# voltage-and-current-display-hw.net
KiCad netlist of a schematic drawn in Altium Designer
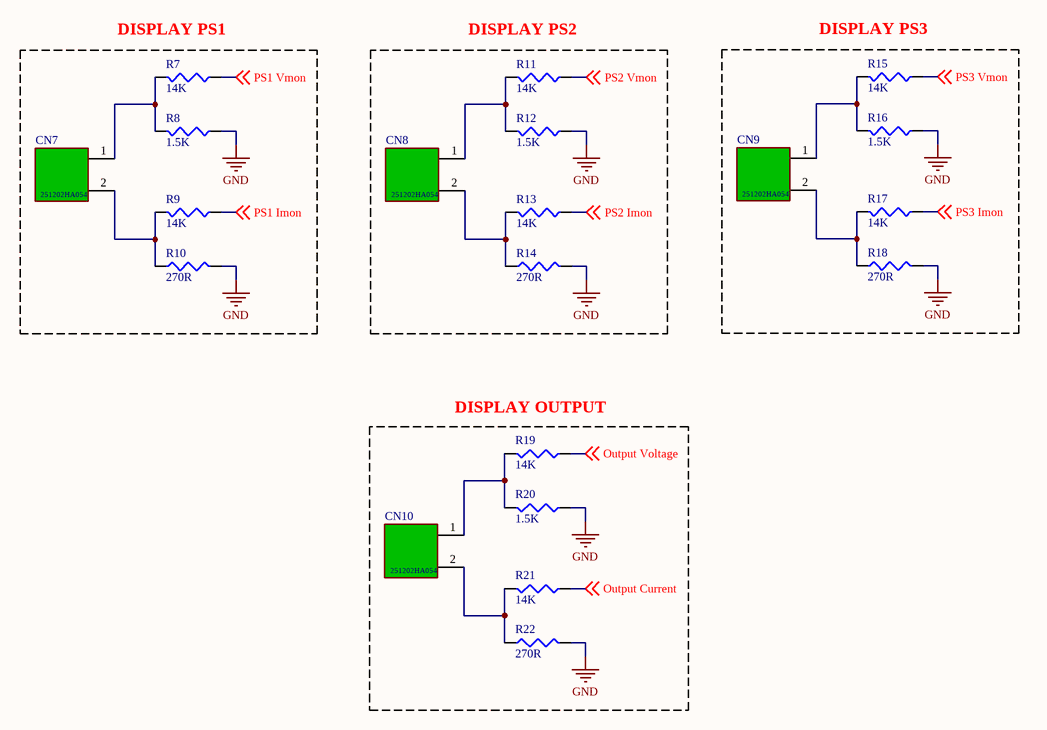
[diagram p0: voltage-and-current-display-hw.SchDoc]

(export (version "E")
  (design (tool "Eeschema 10.0.6"))
  (components
    (comp (ref "CN7")
      (value "Header 2 Pin 251202HA054")
      (footprint "CONECTOR KK EXCON 251202HA054")
      (libsource (lib "acopians-monitoring-hw-library-schematic") (part "CONECTOR KK EXCON 251202HA054"))
    )
    (comp (ref "CN8")
      (value "Header 2 Pin 251202HA054")
      (footprint "CONECTOR KK EXCON 251202HA054")
      (libsource (lib "acopians-monitoring-hw-library-schematic") (part "CONECTOR KK EXCON 251202HA054"))
    )
    (comp (ref "CN9")
      (value "Header 2 Pin 251202HA054")
      (footprint "CONECTOR KK EXCON 251202HA054")
      (libsource (lib "acopians-monitoring-hw-library-schematic") (part "CONECTOR KK EXCON 251202HA054"))
    )
    (comp (ref "CN10")
      (value "Header 2 Pin 251202HA054")
      (footprint "CONECTOR KK EXCON 251202HA054")
      (libsource (lib "acopians-monitoring-hw-library-schematic") (part "CONECTOR KK EXCON 251202HA054"))
    )
    (comp (ref "R7")
      (value "14K")
      (footprint "R0603")
      (description "Resistor SMD 14K OHM 0.1% 1/10W 0603")
      (fields (field (name "TOLERANCE") "0.1%"))
      (libsource (lib "acopians-monitoring-hw-library-schematic") (part "RESISTOR 14K"))
    )
    (comp (ref "R8")
      (value "1.5K")
      (footprint "R0603")
      (description "Resistor SMD 1.5K OHM 0.1% 1/10W 0603")
      (fields (field (name "TOLERANCE") "0.1%"))
      (libsource (lib "acopians-monitoring-hw-library-schematic") (part "RESISTOR 1.5K"))
    )
    (comp (ref "R9")
      (value "14K")
      (footprint "R0603")
      (description "Resistor SMD 14K OHM 0.1% 1/10W 0603")
      (fields (field (name "TOLERANCE") "0.1%"))
      (libsource (lib "acopians-monitoring-hw-library-schematic") (part "RESISTOR 14K"))
    )
    (comp (ref "R10")
      (value "270R")
      (footprint "R0603")
      (description "Resistor SMD 270 OHM 1% 1/10W 0603")
      (fields (field (name "TOLERANCE") "1%"))
      (libsource (lib "acopians-monitoring-hw-library-schematic") (part "RESISTOR 270R"))
    )
    (comp (ref "R11")
      (value "14K")
      (footprint "R0603")
      (description "Resistor SMD 14K OHM 0.1% 1/10W 0603")
      (fields (field (name "TOLERANCE") "0.1%"))
      (libsource (lib "acopians-monitoring-hw-library-schematic") (part "RESISTOR 14K"))
    )
    (comp (ref "R12")
      (value "1.5K")
      (footprint "R0603")
      (description "Resistor SMD 1.5K OHM 0.1% 1/10W 0603")
      (fields (field (name "TOLERANCE") "0.1%"))
      (libsource (lib "acopians-monitoring-hw-library-schematic") (part "RESISTOR 1.5K"))
    )
    (comp (ref "R13")
      (value "14K")
      (footprint "R0603")
      (description "Resistor SMD 14K OHM 0.1% 1/10W 0603")
      (fields (field (name "TOLERANCE") "0.1%"))
      (libsource (lib "acopians-monitoring-hw-library-schematic") (part "RESISTOR 14K"))
    )
    (comp (ref "R14")
      (value "270R")
      (footprint "R0603")
      (description "Resistor SMD 270 OHM 1% 1/10W 0603")
      (fields (field (name "TOLERANCE") "1%"))
      (libsource (lib "acopians-monitoring-hw-library-schematic") (part "RESISTOR 270R"))
    )
    (comp (ref "R15")
      (value "14K")
      (footprint "R0603")
      (description "Resistor SMD 14K OHM 0.1% 1/10W 0603")
      (fields (field (name "TOLERANCE") "0.1%"))
      (libsource (lib "acopians-monitoring-hw-library-schematic") (part "RESISTOR 14K"))
    )
    (comp (ref "R16")
      (value "1.5K")
      (footprint "R0603")
      (description "Resistor SMD 1.5K OHM 0.1% 1/10W 0603")
      (fields (field (name "TOLERANCE") "0.1%"))
      (libsource (lib "acopians-monitoring-hw-library-schematic") (part "RESISTOR 1.5K"))
    )
    (comp (ref "R17")
      (value "14K")
      (footprint "R0603")
      (description "Resistor SMD 14K OHM 0.1% 1/10W 0603")
      (fields (field (name "TOLERANCE") "0.1%"))
      (libsource (lib "acopians-monitoring-hw-library-schematic") (part "RESISTOR 14K"))
    )
    (comp (ref "R18")
      (value "270R")
      (footprint "R0603")
      (description "Resistor SMD 270 OHM 1% 1/10W 0603")
      (fields (field (name "TOLERANCE") "1%"))
      (libsource (lib "acopians-monitoring-hw-library-schematic") (part "RESISTOR 270R"))
    )
    (comp (ref "R19")
      (value "14K")
      (footprint "R0603")
      (description "Resistor SMD 14K OHM 0.1% 1/10W 0603")
      (fields (field (name "TOLERANCE") "0.1%"))
      (libsource (lib "acopians-monitoring-hw-library-schematic") (part "RESISTOR 14K"))
    )
    (comp (ref "R20")
      (value "1.5K")
      (footprint "R0603")
      (description "Resistor SMD 1.5K OHM 0.1% 1/10W 0603")
      (fields (field (name "TOLERANCE") "0.1%"))
      (libsource (lib "acopians-monitoring-hw-library-schematic") (part "RESISTOR 1.5K"))
    )
    (comp (ref "R21")
      (value "14K")
      (footprint "R0603")
      (description "Resistor SMD 14K OHM 0.1% 1/10W 0603")
      (fields (field (name "TOLERANCE") "0.1%"))
      (libsource (lib "acopians-monitoring-hw-library-schematic") (part "RESISTOR 14K"))
    )
    (comp (ref "R22")
      (value "270R")
      (footprint "R0603")
      (description "Resistor SMD 270 OHM 1% 1/10W 0603")
      (fields (field (name "TOLERANCE") "1%"))
      (libsource (lib "acopians-monitoring-hw-library-schematic") (part "RESISTOR 270R"))
    )
  )
  (nets
    (net (code "1") (name "GND") (class "Default")
      (node (ref "R10") (pin "2") (pinfunction "2_2") (pintype "passive"))
      (node (ref "R12") (pin "1") (pinfunction "1_1") (pintype "passive"))
      (node (ref "R14") (pin "2") (pinfunction "2_2") (pintype "passive"))
      (node (ref "R16") (pin "1") (pinfunction "1_1") (pintype "passive"))
      (node (ref "R18") (pin "2") (pinfunction "2_2") (pintype "passive"))
      (node (ref "R20") (pin "1") (pinfunction "1_1") (pintype "passive"))
      (node (ref "R22") (pin "2") (pinfunction "2_2") (pintype "passive"))
      (node (ref "R8") (pin "1") (pinfunction "1_1") (pintype "passive"))
    )
    (net (code "2") (name "Net-(CN7-Pad1)") (class "Default")
      (node (ref "CN7") (pin "1") (pinfunction "1_1") (pintype "passive"))
      (node (ref "R7") (pin "2") (pinfunction "2_2") (pintype "passive"))
      (node (ref "R8") (pin "2") (pinfunction "2_2") (pintype "passive"))
    )
    (net (code "3") (name "Net-(CN7-Pad2)") (class "Default")
      (node (ref "CN7") (pin "2") (pinfunction "2_2") (pintype "passive"))
      (node (ref "R10") (pin "1") (pinfunction "1_1") (pintype "passive"))
      (node (ref "R9") (pin "2") (pinfunction "2_2") (pintype "passive"))
    )
    (net (code "4") (name "Net-(CN8-Pad1)") (class "Default")
      (node (ref "CN8") (pin "1") (pinfunction "1_1") (pintype "passive"))
      (node (ref "R11") (pin "2") (pinfunction "2_2") (pintype "passive"))
      (node (ref "R12") (pin "2") (pinfunction "2_2") (pintype "passive"))
    )
    (net (code "5") (name "Net-(CN8-Pad2)") (class "Default")
      (node (ref "CN8") (pin "2") (pinfunction "2_2") (pintype "passive"))
      (node (ref "R13") (pin "2") (pinfunction "2_2") (pintype "passive"))
      (node (ref "R14") (pin "1") (pinfunction "1_1") (pintype "passive"))
    )
    (net (code "6") (name "Net-(CN9-Pad1)") (class "Default")
      (node (ref "CN9") (pin "1") (pinfunction "1_1") (pintype "passive"))
      (node (ref "R15") (pin "2") (pinfunction "2_2") (pintype "passive"))
      (node (ref "R16") (pin "2") (pinfunction "2_2") (pintype "passive"))
    )
    (net (code "7") (name "Net-(CN9-Pad2)") (class "Default")
      (node (ref "CN9") (pin "2") (pinfunction "2_2") (pintype "passive"))
      (node (ref "R17") (pin "2") (pinfunction "2_2") (pintype "passive"))
      (node (ref "R18") (pin "1") (pinfunction "1_1") (pintype "passive"))
    )
    (net (code "8") (name "Net-(CN10-Pad1)") (class "Default")
      (node (ref "CN10") (pin "1") (pinfunction "1_1") (pintype "passive"))
      (node (ref "R19") (pin "2") (pinfunction "2_2") (pintype "passive"))
      (node (ref "R20") (pin "2") (pinfunction "2_2") (pintype "passive"))
    )
    (net (code "9") (name "Net-(CN10-Pad2)") (class "Default")
      (node (ref "CN10") (pin "2") (pinfunction "2_2") (pintype "passive"))
      (node (ref "R21") (pin "2") (pinfunction "2_2") (pintype "passive"))
      (node (ref "R22") (pin "1") (pinfunction "1_1") (pintype "passive"))
    )
    (net (code "10") (name "Output Current") (class "Default")
      (node (ref "R21") (pin "1") (pinfunction "1_1") (pintype "passive"))
    )
    (net (code "11") (name "Output Voltage") (class "Default")
      (node (ref "R19") (pin "1") (pinfunction "1_1") (pintype "passive"))
    )
    (net (code "12") (name "PS1 Imon") (class "Default")
      (node (ref "R9") (pin "1") (pinfunction "1_1") (pintype "passive"))
    )
    (net (code "13") (name "PS1 Vmon") (class "Default")
      (node (ref "R7") (pin "1") (pinfunction "1_1") (pintype "passive"))
    )
    (net (code "14") (name "PS2 Imon") (class "Default")
      (node (ref "R13") (pin "1") (pinfunction "1_1") (pintype "passive"))
    )
    (net (code "15") (name "PS2 Vmon") (class "Default")
      (node (ref "R11") (pin "1") (pinfunction "1_1") (pintype "passive"))
    )
    (net (code "16") (name "PS3 Imon") (class "Default")
      (node (ref "R17") (pin "1") (pinfunction "1_1") (pintype "passive"))
    )
    (net (code "17") (name "PS3 Vmon") (class "Default")
      (node (ref "R15") (pin "1") (pinfunction "1_1") (pintype "passive"))
    )
  )
)
